# CW308T_LPC1343.net
KiCad netlist of a schematic drawn in Altium Designer
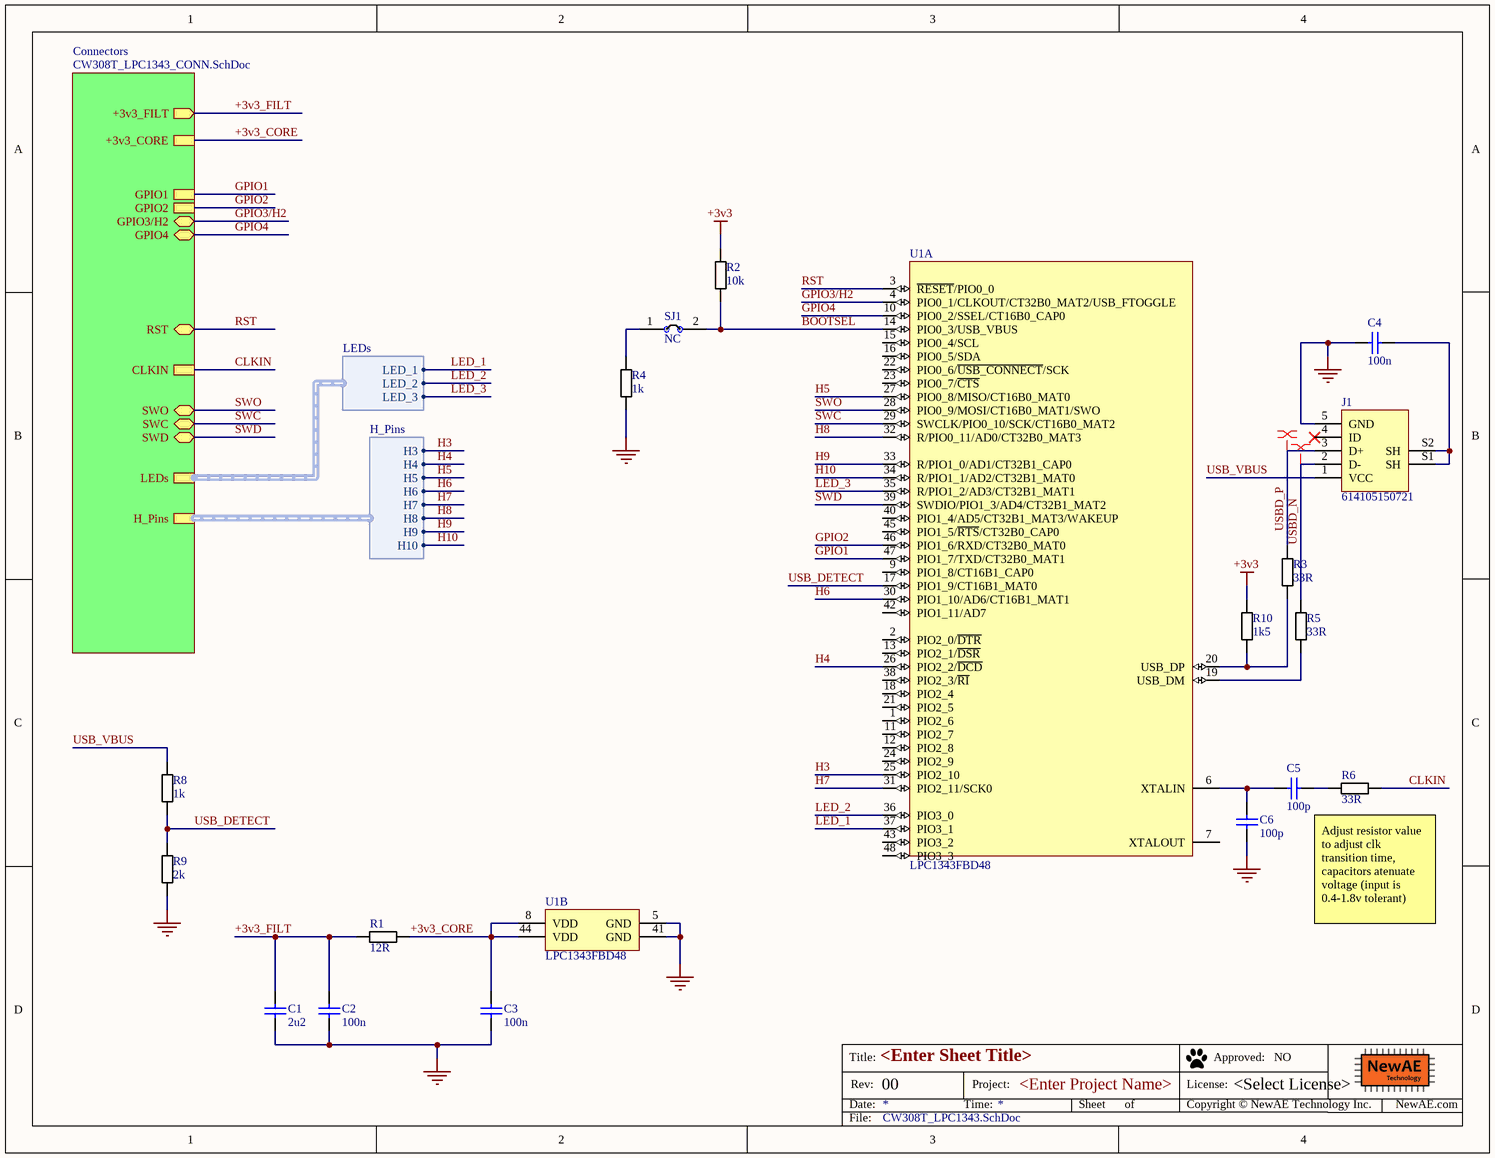
[diagram p0: CW308T_LPC1343.SchDoc]

(export (version "E")
  (design (tool "Eeschema 10.0.6"))
  (components
    (comp (ref "C1")
      (value "2u2")
      (footprint "CAPC0603_M")
      (description "2u2, 0603")
      (fields (field (name "PART NUMBER") "CCHIP-2u2-0603"))
      (libsource (lib "NewAE_AltiumLib") (part "CAP"))
    )
    (comp (ref "C2")
      (value "100n")
      (footprint "CAPC0603_M")
      (description "100n, 0603")
      (fields (field (name "PART NUMBER") "CCHIP-100n-0603"))
      (libsource (lib "NewAE_AltiumLib") (part "CAP"))
    )
    (comp (ref "C3")
      (value "100n")
      (footprint "CAPC0603_M")
      (description "100n, 0603")
      (fields (field (name "PART NUMBER") "CCHIP-100n-0603"))
      (libsource (lib "NewAE_AltiumLib") (part "CAP"))
    )
    (comp (ref "C4")
      (value "100n")
      (footprint "CAPC0603_M")
      (description "100n, 0603")
      (fields (field (name "PART NUMBER") "CCHIP-100n-0603"))
      (libsource (lib "NewAE_AltiumLib") (part "CAP"))
    )
    (comp (ref "C5")
      (value "100p")
      (footprint "CAPC0603_M")
      (description "100p, 0603")
      (fields (field (name "PART NUMBER") "CCHIP-100p-0603"))
      (libsource (lib "NewAE_AltiumLib") (part "CAP"))
    )
    (comp (ref "C6")
      (value "100p")
      (footprint "CAPC0603_M")
      (description "100p, 0603")
      (fields (field (name "PART NUMBER") "CCHIP-100p-0603"))
      (libsource (lib "NewAE_AltiumLib") (part "CAP"))
    )
    (comp (ref "J1")
      (value "614105150721")
      (footprint "614105150721")
      (description "USB, 5-pin, Upright")
      (libsource (lib "NewAE_AltiumLib") (part "USB_5PIN_2SHIELD"))
    )
    (comp (ref "R1")
      (value "12R")
      (footprint "RESC1608X55N")
      (description "12R res, 0603, 1%, 1/10W")
      (fields (field (name "PART NUMBER") "RCHIP-12R-0603") (field (name "TOLERANCE") "1%"))
      (libsource (lib "NewAE_AltiumLib") (part "RES-EU"))
    )
    (comp (ref "R2")
      (value "10k")
      (footprint "RESC1608X55N")
      (description "10k res, 0603, 1%, 1/10W")
      (fields (field (name "PART NUMBER") "RCHIP-10K-0603") (field (name "TOLERANCE") "1%"))
      (libsource (lib "") (part "RES-EU_1"))
    )
    (comp (ref "R3")
      (value "33R")
      (footprint "RESC1608X55N")
      (description "33R res, 0603, 1%, 1/10W")
      (fields (field (name "PART NUMBER") "RCHIP-33R-0603") (field (name "TOLERANCE") "1%"))
      (libsource (lib "") (part "RES-EU_1"))
    )
    (comp (ref "R4")
      (value "1k")
      (footprint "RESC1608X55N")
      (description "1k res, 0603, 1%, 1/10W")
      (fields (field (name "PART NUMBER") "RCHIP-1K-0603") (field (name "TOLERANCE") "1%"))
      (libsource (lib "") (part "RES-EU_1"))
    )
    (comp (ref "R5")
      (value "33R")
      (footprint "RESC1608X55N")
      (description "33R res, 0603, 1%, 1/10W")
      (fields (field (name "PART NUMBER") "RCHIP-33R-0603") (field (name "TOLERANCE") "1%"))
      (libsource (lib "") (part "RES-EU_1"))
    )
    (comp (ref "R6")
      (value "33R")
      (footprint "RESC1608X55N")
      (description "33R res, 0603, 1%, 1/10W")
      (fields (field (name "PART NUMBER") "RCHIP-33R-0603") (field (name "TOLERANCE") "1%"))
      (libsource (lib "NewAE_AltiumLib") (part "RES-EU"))
    )
    (comp (ref "R8")
      (value "1k")
      (footprint "RESC1608X55N")
      (description "1k res, 0603, 1%, 1/10W")
      (fields (field (name "PART NUMBER") "RCHIP-1K-0603") (field (name "TOLERANCE") "1%"))
      (libsource (lib "") (part "RES-EU_1"))
    )
    (comp (ref "R9")
      (value "2k")
      (footprint "RESC1608X55N")
      (description "2k res, 0603, 1%, 1/10W")
      (fields (field (name "PART NUMBER") "RCHIP-2K-0603") (field (name "TOLERANCE") "1%"))
      (libsource (lib "") (part "RES-EU_1"))
    )
    (comp (ref "R10")
      (value "1k5")
      (footprint "RESC1608X55N")
      (description "1k5 res, 0603, 1%, 1/10W")
      (fields (field (name "PART NUMBER") "RCHIP-1K5-0603") (field (name "TOLERANCE") "1%"))
      (libsource (lib "") (part "RES-EU_1"))
    )
    (comp (ref "SJ1")
      (value "NC")
      (footprint "SJ_2S_NC")
      (description "Solder Jumper, NC")
      (fields (field (name "PART NUMBER") "SJ_2S"))
      (libsource (lib "NewAE_AltiumLib") (part "SJ_2S"))
    )
    (comp (ref "U1") (value "LPC1343FBD48") (libsource (lib "NewAE_AltiumLib") (part "LPC1343FBD48")))
  )
  (nets
    (net (code "3") (name "+3v3") (class "Default")
      (node (ref "R10") (pin "1") (pinfunction "1_1") (pintype "passive"))
      (node (ref "R2") (pin "1") (pinfunction "1_1") (pintype "passive"))
    )
    (net (code "4") (name "/+3v3_CORE") (class "Default")
      (node (ref "C3") (pin "1") (pinfunction "1_1") (pintype "passive"))
      (node (ref "R1") (pin "2") (pinfunction "2_2") (pintype "passive"))
      (node (ref "U1") (pin "44") (pinfunction "VDD_44") (pintype "power_in"))
      (node (ref "U1") (pin "8") (pinfunction "VDD_8") (pintype "power_in"))
    )
    (net (code "5") (name "/+3v3_FILT") (class "Default")
      (node (ref "C1") (pin "1") (pinfunction "1_1") (pintype "passive"))
      (node (ref "C2") (pin "1") (pinfunction "1_1") (pintype "passive"))
      (node (ref "R1") (pin "1") (pinfunction "1_1") (pintype "passive"))
    )
    (net (code "6") (name "/BOOTSEL") (class "Default")
      (node (ref "R2") (pin "2") (pinfunction "2_2") (pintype "passive"))
      (node (ref "SJ1") (pin "2") (pinfunction "2_2") (pintype "passive"))
      (node (ref "U1") (pin "14") (pinfunction "PIO0_3/USB_VBUS_14") (pintype "bidirectional"))
    )
    (net (code "7") (name "/CLKIN") (class "Default")
      (node (ref "R6") (pin "2") (pinfunction "2_2") (pintype "passive"))
    )
    (net (code "8") (name "/GPIO1") (class "Default")
      (node (ref "U1") (pin "47") (pinfunction "PIO1_7/TXD/CT32B0_MAT1_47") (pintype "bidirectional"))
    )
    (net (code "9") (name "/GPIO2") (class "Default")
      (node (ref "U1") (pin "46") (pinfunction "PIO1_6/RXD/CT32B0_MAT0_46") (pintype "bidirectional"))
    )
    (net (code "10") (name "/GPIO3{slash}H2") (class "Default")
      (node (ref "U1") (pin "4") (pinfunction "PIO0_1/CLKOUT/CT32B0_MAT2/USB_FTOGGLE_4") (pintype "bidirectional"))
    )
    (net (code "11") (name "/GPIO4") (class "Default")
      (node (ref "U1") (pin "10") (pinfunction "PIO0_2/SSEL/CT16B0_CAP0_10") (pintype "bidirectional"))
    )
    (net (code "12") (name "/H3") (class "Default")
      (node (ref "U1") (pin "25") (pinfunction "PIO2_10_25") (pintype "bidirectional"))
    )
    (net (code "13") (name "/H4") (class "Default")
      (node (ref "U1") (pin "26") (pinfunction "PIO2_2/~{DCD}_26") (pintype "bidirectional"))
    )
    (net (code "14") (name "/H5") (class "Default")
      (node (ref "U1") (pin "27") (pinfunction "PIO0_8/MISO/CT16B0_MAT0_27") (pintype "bidirectional"))
    )
    (net (code "15") (name "/H6") (class "Default")
      (node (ref "U1") (pin "30") (pinfunction "PIO1_10/AD6/CT16B1_MAT1_30") (pintype "bidirectional"))
    )
    (net (code "16") (name "/H7") (class "Default")
      (node (ref "U1") (pin "31") (pinfunction "PIO2_11/SCK0_31") (pintype "bidirectional"))
    )
    (net (code "17") (name "/H8") (class "Default")
      (node (ref "U1") (pin "32") (pinfunction "R/PIO0_11/AD0/CT32B0_MAT3_32") (pintype "bidirectional"))
    )
    (net (code "18") (name "/H9") (class "Default")
      (node (ref "U1") (pin "33") (pinfunction "R/PIO1_0/AD1/CT32B1_CAP0_33") (pintype "bidirectional"))
    )
    (net (code "19") (name "/H10") (class "Default")
      (node (ref "U1") (pin "34") (pinfunction "R/PIO1_1/AD2/CT32B1_MAT0_34") (pintype "bidirectional"))
    )
    (net (code "20") (name "/LED_1") (class "Default")
      (node (ref "U1") (pin "37") (pinfunction "PIO3_1_37") (pintype "bidirectional"))
    )
    (net (code "21") (name "/LED_2") (class "Default")
      (node (ref "U1") (pin "36") (pinfunction "PIO3_0_36") (pintype "bidirectional"))
    )
    (net (code "22") (name "/LED_3") (class "Default")
      (node (ref "U1") (pin "35") (pinfunction "R/PIO1_2/AD3/CT32B1_MAT1_35") (pintype "bidirectional"))
    )
    (net (code "23") (name "/RST") (class "Default")
      (node (ref "U1") (pin "3") (pinfunction "~{RESET}/PIO0_0_3") (pintype "bidirectional"))
    )
    (net (code "24") (name "/SWC") (class "Default")
      (node (ref "U1") (pin "29") (pinfunction "SWCLK/PIO0_10/SCK/CT16B0_MAT2_29") (pintype "bidirectional"))
    )
    (net (code "25") (name "/SWD") (class "Default")
      (node (ref "U1") (pin "39") (pinfunction "SWDIO/PIO1_3/AD4/CT32B1_MAT2_39") (pintype "bidirectional"))
    )
    (net (code "26") (name "/SWO") (class "Default")
      (node (ref "U1") (pin "28") (pinfunction "PIO0_9/MOSI/CT16B0_MAT1/SWO_28") (pintype "bidirectional"))
    )
    (net (code "27") (name "/USBD_N") (class "Default")
      (node (ref "J1") (pin "2") (pinfunction "D-_2") (pintype "passive"))
      (node (ref "R5") (pin "1") (pinfunction "1_1") (pintype "passive"))
    )
    (net (code "28") (name "/USBD_P") (class "Default")
      (node (ref "J1") (pin "3") (pinfunction "D+_3") (pintype "passive"))
      (node (ref "R3") (pin "1") (pinfunction "1_1") (pintype "passive"))
    )
    (net (code "29") (name "/USB_DETECT") (class "Default")
      (node (ref "R8") (pin "2") (pinfunction "2_2") (pintype "passive"))
      (node (ref "R9") (pin "1") (pinfunction "1_1") (pintype "passive"))
      (node (ref "U1") (pin "17") (pinfunction "PIO1_9/CT16B1_MAT0_17") (pintype "bidirectional"))
    )
    (net (code "30") (name "/USB_VBUS") (class "Default")
      (node (ref "J1") (pin "1") (pinfunction "VCC_1") (pintype "passive"))
      (node (ref "R8") (pin "1") (pinfunction "1_1") (pintype "passive"))
    )
    (net (code "33") (name "GND") (class "Default")
      (node (ref "C1") (pin "2") (pinfunction "2_2") (pintype "passive"))
      (node (ref "C2") (pin "2") (pinfunction "2_2") (pintype "passive"))
      (node (ref "C3") (pin "2") (pinfunction "2_2") (pintype "passive"))
      (node (ref "C4") (pin "1") (pinfunction "1_1") (pintype "passive"))
      (node (ref "C6") (pin "2") (pinfunction "2_2") (pintype "passive"))
      (node (ref "J1") (pin "5") (pinfunction "GND_5") (pintype "power_in"))
      (node (ref "R4") (pin "2") (pinfunction "2_2") (pintype "passive"))
      (node (ref "R9") (pin "2") (pinfunction "2_2") (pintype "passive"))
      (node (ref "U1") (pin "41") (pinfunction "GND_41") (pintype "power_in"))
      (node (ref "U1") (pin "5") (pinfunction "GND_5") (pintype "power_in"))
    )
    (net (code "34") (name "Net-(C4-Pad2)") (class "Default")
      (node (ref "C4") (pin "2") (pinfunction "2_2") (pintype "passive"))
      (node (ref "J1") (pin "S1") (pinfunction "SH_S1") (pintype "passive"))
      (node (ref "J1") (pin "S2") (pinfunction "SH_S2") (pintype "passive"))
    )
    (net (code "35") (name "Net-(C5-Pad2)") (class "Default")
      (node (ref "C5") (pin "2") (pinfunction "2_2") (pintype "passive"))
      (node (ref "R6") (pin "1") (pinfunction "1_1") (pintype "passive"))
    )
    (net (code "36") (name "Net-(R4-Pad1)") (class "Default")
      (node (ref "R4") (pin "1") (pinfunction "1_1") (pintype "passive"))
      (node (ref "SJ1") (pin "1") (pinfunction "1_1") (pintype "passive"))
    )
    (net (code "37") (name "Net-(U1A-USB_DM)") (class "Default")
      (node (ref "R5") (pin "2") (pinfunction "2_2") (pintype "passive"))
      (node (ref "U1") (pin "19") (pinfunction "USB_DM_19") (pintype "bidirectional"))
    )
    (net (code "38") (name "Net-(U1A-USB_DP)") (class "Default")
      (node (ref "R10") (pin "2") (pinfunction "2_2") (pintype "passive"))
      (node (ref "R3") (pin "2") (pinfunction "2_2") (pintype "passive"))
      (node (ref "U1") (pin "20") (pinfunction "USB_DP_20") (pintype "bidirectional"))
    )
    (net (code "39") (name "Net-(U1A-XTALIN)") (class "Default")
      (node (ref "C5") (pin "1") (pinfunction "1_1") (pintype "passive"))
      (node (ref "C6") (pin "1") (pinfunction "1_1") (pintype "passive"))
      (node (ref "U1") (pin "6") (pinfunction "XTALIN_6") (pintype "passive"))
    )
    (net (code "40") (name "unconnected-(J1-ID-Pad4)") (class "Default")
      (node (ref "J1") (pin "4") (pinfunction "ID_4") (pintype "power_in+no_connect"))
    )
    (net (code "41") (name "unconnected-(U1A-PIO0_4{slash}SCL-Pad15)") (class "Default")
      (node (ref "U1") (pin "15") (pinfunction "PIO0_4/SCL_15") (pintype "bidirectional"))
    )
    (net (code "42") (name "unconnected-(U1A-PIO0_5{slash}SDA-Pad16)") (class "Default")
      (node (ref "U1") (pin "16") (pinfunction "PIO0_5/SDA_16") (pintype "bidirectional"))
    )
    (net (code "43") (name "unconnected-(U1A-PIO0_6{slash}~{USB_CONNECT}{slash}SCK-Pad22)") (class "Default")
      (node (ref "U1") (pin "22") (pinfunction "PIO0_6/~{USB_CONNECT}/SCK_22") (pintype "bidirectional"))
    )
    (net (code "44") (name "unconnected-(U1A-PIO0_7{slash}~{CTS}-Pad23)") (class "Default")
      (node (ref "U1") (pin "23") (pinfunction "PIO0_7/~{CTS}_23") (pintype "bidirectional"))
    )
    (net (code "45") (name "unconnected-(U1A-PIO1_4{slash}AD5{slash}CT32B1_MAT3{slash}WAKEUP-Pad40)") (class "Default")
      (node (ref "U1") (pin "40") (pinfunction "PIO1_4/AD5/CT32B1_MAT3/WAKEUP_40") (pintype "bidirectional"))
    )
    (net (code "46") (name "unconnected-(U1A-PIO1_5{slash}~{RTS}{slash}CT32B0_CAP0-Pad45)") (class "Default")
      (node (ref "U1") (pin "45") (pinfunction "PIO1_5/~{RTS}/CT32B0_CAP0_45") (pintype "bidirectional"))
    )
    (net (code "47") (name "unconnected-(U1A-PIO1_8{slash}CT16B1_CAP0-Pad9)") (class "Default")
      (node (ref "U1") (pin "9") (pinfunction "PIO1_8/CT16B1_CAP0_9") (pintype "bidirectional"))
    )
    (net (code "48") (name "unconnected-(U1A-PIO1_11{slash}AD7-Pad42)") (class "Default")
      (node (ref "U1") (pin "42") (pinfunction "PIO1_11/AD7_42") (pintype "bidirectional"))
    )
    (net (code "49") (name "unconnected-(U1A-PIO2_0{slash}~{DTR}-Pad2)") (class "Default")
      (node (ref "U1") (pin "2") (pinfunction "PIO2_0/~{DTR}_2") (pintype "bidirectional"))
    )
    (net (code "50") (name "unconnected-(U1A-PIO2_1{slash}~{DSR}-Pad13)") (class "Default")
      (node (ref "U1") (pin "13") (pinfunction "PIO2_1/~{DSR}_13") (pintype "bidirectional"))
    )
    (net (code "51") (name "unconnected-(U1A-PIO2_3{slash}~{RI}-Pad38)") (class "Default")
      (node (ref "U1") (pin "38") (pinfunction "PIO2_3/~{RI}_38") (pintype "bidirectional"))
    )
    (net (code "52") (name "unconnected-(U1A-PIO2_4-Pad18)") (class "Default")
      (node (ref "U1") (pin "18") (pinfunction "PIO2_4_18") (pintype "bidirectional"))
    )
    (net (code "53") (name "unconnected-(U1A-PIO2_5-Pad21)") (class "Default")
      (node (ref "U1") (pin "21") (pinfunction "PIO2_5_21") (pintype "bidirectional"))
    )
    (net (code "54") (name "unconnected-(U1A-PIO2_6-Pad1)") (class "Default")
      (node (ref "U1") (pin "1") (pinfunction "PIO2_6_1") (pintype "bidirectional"))
    )
    (net (code "55") (name "unconnected-(U1A-PIO2_7-Pad11)") (class "Default")
      (node (ref "U1") (pin "11") (pinfunction "PIO2_7_11") (pintype "bidirectional"))
    )
    (net (code "56") (name "unconnected-(U1A-PIO2_8-Pad12)") (class "Default")
      (node (ref "U1") (pin "12") (pinfunction "PIO2_8_12") (pintype "bidirectional"))
    )
    (net (code "57") (name "unconnected-(U1A-PIO2_9-Pad24)") (class "Default")
      (node (ref "U1") (pin "24") (pinfunction "PIO2_9_24") (pintype "bidirectional"))
    )
    (net (code "58") (name "unconnected-(U1A-PIO3_2-Pad43)") (class "Default")
      (node (ref "U1") (pin "43") (pinfunction "PIO3_2_43") (pintype "bidirectional"))
    )
    (net (code "59") (name "unconnected-(U1A-PIO3_3-Pad48)") (class "Default")
      (node (ref "U1") (pin "48") (pinfunction "PIO3_3_48") (pintype "bidirectional"))
    )
    (net (code "60") (name "unconnected-(U1A-XTALOUT-Pad7)") (class "Default")
      (node (ref "U1") (pin "7") (pinfunction "XTALOUT_7") (pintype "passive"))
    )
  )
)
